# p3_fan_regulator.net
KiCad netlist of a schematic drawn in Altium Designer
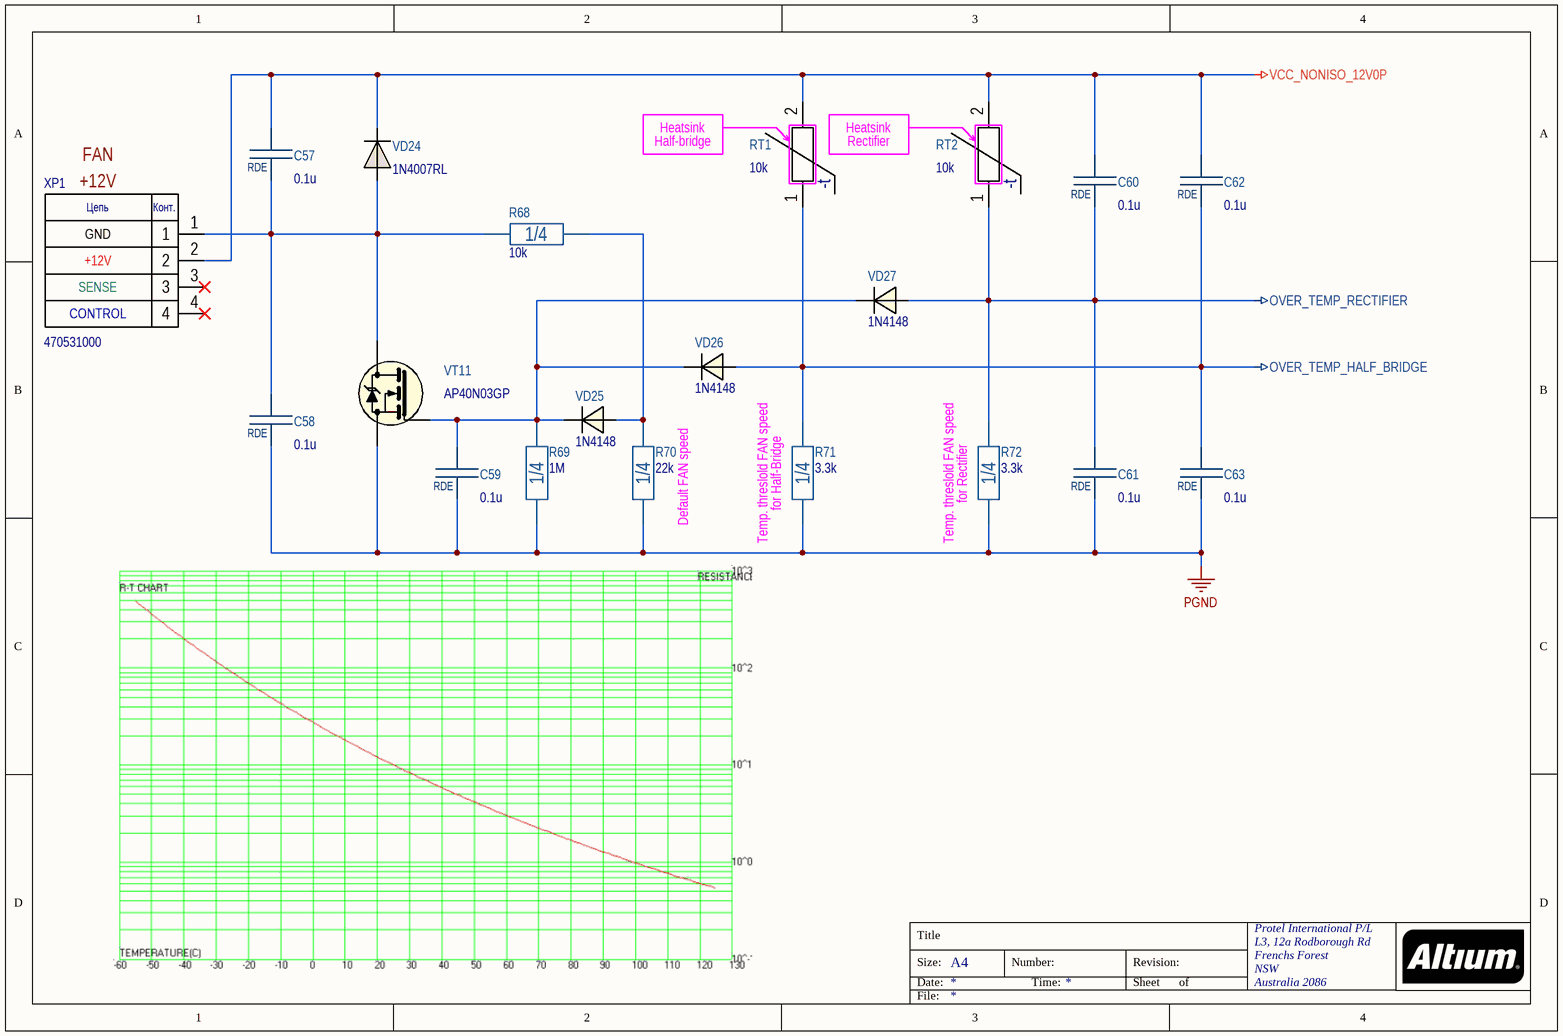
[diagram p0: p3_fan_regulator.SchDoc]

(export (version "E")
  (design (tool "Eeschema 10.0.6"))
  (components
    (comp (ref "C57")
      (value "0.1u")
      (footprint "PcbLib_RC:RDE_1P1")
      (description "MLCC radial lead type with epoxy coat (RDE Series)")
      (fields
        (field (name "TOLERANCE") "± 10 %")
        (field (name "VOLTAGE") "100V")
        (field (name "PACKAGE") "RDE")
      )
      (libsource (lib "Schlib_RC") (part "RDE_CAP"))
    )
    (comp (ref "C58")
      (value "0.1u")
      (footprint "PcbLib_RC:RDE_1P1")
      (description "MLCC radial lead type with epoxy coat (RDE Series)")
      (fields
        (field (name "TOLERANCE") "± 10 %")
        (field (name "VOLTAGE") "100V")
        (field (name "PACKAGE") "RDE")
      )
      (libsource (lib "Schlib_RC") (part "RDE_CAP"))
    )
    (comp (ref "C59")
      (value "0.1u")
      (footprint "PcbLib_RC:RDE_1P1")
      (description "MLCC radial lead type with epoxy coat (RDE Series)")
      (fields
        (field (name "TOLERANCE") "± 10 %")
        (field (name "VOLTAGE") "100V")
        (field (name "PACKAGE") "RDE")
      )
      (libsource (lib "Schlib_RC") (part "RDE_CAP"))
    )
    (comp (ref "C60")
      (value "0.1u")
      (footprint "PcbLib_RC:RDE_1P1")
      (description "MLCC radial lead type with epoxy coat (RDE Series)")
      (fields
        (field (name "TOLERANCE") "± 10 %")
        (field (name "VOLTAGE") "100V")
        (field (name "PACKAGE") "RDE")
      )
      (libsource (lib "Schlib_RC") (part "RDE_CAP"))
    )
    (comp (ref "C61")
      (value "0.1u")
      (footprint "PcbLib_RC:RDE_1P1")
      (description "MLCC radial lead type with epoxy coat (RDE Series)")
      (fields
        (field (name "TOLERANCE") "± 10 %")
        (field (name "VOLTAGE") "100V")
        (field (name "PACKAGE") "RDE")
      )
      (libsource (lib "Schlib_RC") (part "RDE_CAP"))
    )
    (comp (ref "C62")
      (value "0.1u")
      (footprint "PcbLib_RC:RDE_1P1")
      (description "MLCC radial lead type with epoxy coat (RDE Series)")
      (fields
        (field (name "TOLERANCE") "± 10 %")
        (field (name "VOLTAGE") "100V")
        (field (name "PACKAGE") "RDE")
      )
      (libsource (lib "Schlib_RC") (part "RDE_CAP"))
    )
    (comp (ref "C63")
      (value "0.1u")
      (footprint "PcbLib_RC:RDE_1P1")
      (description "MLCC radial lead type with epoxy coat (RDE Series)")
      (fields
        (field (name "TOLERANCE") "± 10 %")
        (field (name "VOLTAGE") "100V")
        (field (name "PACKAGE") "RDE")
      )
      (libsource (lib "Schlib_RC") (part "RDE_CAP"))
    )
    (comp (ref "R68")
      (value "10k")
      (footprint "PcbLib_RC:CFR-25")
      (description "Resistor 1/4W")
      (fields
        (field (name "TOLERANCE") "± 1 %")
        (field (name "PART NUMBER") "MFR-25FTF52-10K")
        (field (name "PACKAGE") "1/4")
      )
      (libsource (lib "Schlib_RC") (part "CF25"))
    )
    (comp (ref "R69")
      (value "1M")
      (footprint "PcbLib_RC:CFR-25(VERTICAL)")
      (description "Resistor 1/4W")
      (fields
        (field (name "TOLERANCE") "± 1 %")
        (field (name "PART NUMBER") "MFR-25FTF52-1M")
        (field (name "PACKAGE") "1/4")
      )
      (libsource (lib "Schlib_RC") (part "CF25"))
    )
    (comp (ref "R70")
      (value "22k")
      (footprint "PcbLib_RC:CFR-25(VERTICAL)")
      (description "Resistor 1/4W")
      (fields
        (field (name "TOLERANCE") "± 1 %")
        (field (name "PART NUMBER") "MFR-25FTF52-22K")
        (field (name "PACKAGE") "1/4")
      )
      (libsource (lib "Schlib_RC") (part "CF25"))
    )
    (comp (ref "R71")
      (value "3.3k")
      (footprint "PcbLib_RC:CFR-25(VERTICAL)")
      (description "Resistor 1/4W")
      (fields
        (field (name "TOLERANCE") "± 1 %")
        (field (name "PART NUMBER") "MFR-25FTF52-3K3")
        (field (name "PACKAGE") "1/4")
      )
      (libsource (lib "Schlib_RC") (part "CF25"))
    )
    (comp (ref "R72")
      (value "3.3k")
      (footprint "PcbLib_RC:CFR-25(VERTICAL)")
      (description "Resistor 1/4W")
      (fields
        (field (name "TOLERANCE") "± 1 %")
        (field (name "PART NUMBER") "MFR-25FTF52-3K3")
        (field (name "PACKAGE") "1/4")
      )
      (libsource (lib "Schlib_RC") (part "CF25"))
    )
    (comp (ref "RT1")
      (value "10k")
      (footprint "PcbLib_Others:NTC_D8")
      (description "NTC thermistors")
      (libsource (lib "Schlib_OtherComponents") (part "NTC"))
    )
    (comp (ref "RT2")
      (value "10k")
      (footprint "PcbLib_Others:NTC_D8")
      (description "NTC thermistors")
      (libsource (lib "Schlib_OtherComponents") (part "NTC"))
    )
    (comp (ref "VD24")
      (value "1N4007RL")
      (footprint "PcbLib_Discrete:DO-41")
      (description "1A 1000V Standard Recovery Rectifiers Diode")
      (fields (field (name "MANUFACTURER") "ON Semiconductor"))
      (libsource (lib "Schlib_ONSemiconductor") (part "1N4007RL"))
    )
    (comp (ref "VD25")
      (value "1N4148")
      (footprint "PcbLib_Discrete:DO-35 GLASS LIGHT RED")
      (description "High-speed diode")
      (libsource (lib "Schlib_NXP_Semiconductors") (part "1N4148"))
    )
    (comp (ref "VD26")
      (value "1N4148")
      (footprint "PcbLib_Discrete:DO-35 GLASS LIGHT RED")
      (description "High-speed diode")
      (libsource (lib "Schlib_NXP_Semiconductors") (part "1N4148"))
    )
    (comp (ref "VD27")
      (value "1N4148")
      (footprint "PcbLib_Discrete:DO-35 GLASS LIGHT RED")
      (description "High-speed diode")
      (libsource (lib "Schlib_NXP_Semiconductors") (part "1N4148"))
    )
    (comp (ref "VT11")
      (value "AP40N03GP")
      (footprint "TO-220A-3")
      (description "N-Channel MOSFET,  30V, 40A")
      (fields (field (name "MANUFACTURER") "Advanced Power Electronics Corp."))
      (libsource (lib "Schlib_OtherComponents") (part "AP40N03GP"))
    )
    (comp (ref "XP1")
      (value "470531000")
      (footprint "PcbLib_Pin_Headers:0470531000")
      (libsource (lib "Schlib_MolexConnectors") (part "470531000"))
    )
  )
  (nets
    (net (code "1") (name "Net-(R68-Pad1)") (class "Default")
      (node (ref "R68") (pin "1") (pinfunction "1_1") (pintype "passive"))
      (node (ref "R70") (pin "2") (pinfunction "2_2") (pintype "passive"))
      (node (ref "VD25") (pin "2") (pinfunction "2_2") (pintype "passive"))
    )
    (net (code "2") (name "Net-(VD24-A)") (class "Default")
      (node (ref "C57") (pin "2") (pinfunction "2_2") (pintype "passive"))
      (node (ref "C58") (pin "1") (pinfunction "1_1") (pintype "passive"))
      (node (ref "R68") (pin "2") (pinfunction "2_2") (pintype "passive"))
      (node (ref "VD24") (pin "2") (pinfunction "A_2") (pintype "passive"))
      (node (ref "VT11") (pin "2") (pinfunction "D_2") (pintype "passive"))
      (node (ref "XP1") (pin "1") (pinfunction "1_1") (pintype "passive"))
    )
    (net (code "3") (name "Net-(VT11-G)") (class "Default")
      (node (ref "C59") (pin "1") (pinfunction "1_1") (pintype "passive"))
      (node (ref "R69") (pin "2") (pinfunction "2_2") (pintype "passive"))
      (node (ref "VD25") (pin "1") (pinfunction "1_1") (pintype "passive"))
      (node (ref "VD26") (pin "1") (pinfunction "1_1") (pintype "passive"))
      (node (ref "VD27") (pin "1") (pinfunction "1_1") (pintype "passive"))
      (node (ref "VT11") (pin "1") (pinfunction "G_1") (pintype "passive"))
    )
    (net (code "4") (name "OVER_TEMP_HALF_BRIDGE") (class "Default")
      (node (ref "C62") (pin "2") (pinfunction "2_2") (pintype "passive"))
      (node (ref "C63") (pin "1") (pinfunction "1_1") (pintype "passive"))
      (node (ref "R71") (pin "2") (pinfunction "2_2") (pintype "passive"))
      (node (ref "RT1") (pin "1") (pinfunction "1_1") (pintype "passive"))
      (node (ref "VD26") (pin "2") (pinfunction "2_2") (pintype "passive"))
    )
    (net (code "5") (name "OVER_TEMP_RECTIFIER") (class "Default")
      (node (ref "C60") (pin "2") (pinfunction "2_2") (pintype "passive"))
      (node (ref "C61") (pin "1") (pinfunction "1_1") (pintype "passive"))
      (node (ref "R72") (pin "2") (pinfunction "2_2") (pintype "passive"))
      (node (ref "RT2") (pin "1") (pinfunction "1_1") (pintype "passive"))
      (node (ref "VD27") (pin "2") (pinfunction "2_2") (pintype "passive"))
    )
    (net (code "6") (name "PGND") (class "Default")
      (node (ref "C58") (pin "2") (pinfunction "2_2") (pintype "passive"))
      (node (ref "C59") (pin "2") (pinfunction "2_2") (pintype "passive"))
      (node (ref "C61") (pin "2") (pinfunction "2_2") (pintype "passive"))
      (node (ref "C63") (pin "2") (pinfunction "2_2") (pintype "passive"))
      (node (ref "R69") (pin "1") (pinfunction "1_1") (pintype "passive"))
      (node (ref "R70") (pin "1") (pinfunction "1_1") (pintype "passive"))
      (node (ref "R71") (pin "1") (pinfunction "1_1") (pintype "passive"))
      (node (ref "R72") (pin "1") (pinfunction "1_1") (pintype "passive"))
      (node (ref "VT11") (pin "3") (pinfunction "S_3") (pintype "passive"))
    )
    (net (code "7") (name "VCC_NONISO_12V0P") (class "Default")
      (node (ref "C57") (pin "1") (pinfunction "1_1") (pintype "passive"))
      (node (ref "C60") (pin "1") (pinfunction "1_1") (pintype "passive"))
      (node (ref "C62") (pin "1") (pinfunction "1_1") (pintype "passive"))
      (node (ref "RT1") (pin "2") (pinfunction "2_2") (pintype "passive"))
      (node (ref "RT2") (pin "2") (pinfunction "2_2") (pintype "passive"))
      (node (ref "VD24") (pin "1") (pinfunction "C_1") (pintype "passive"))
      (node (ref "XP1") (pin "2") (pinfunction "2_2") (pintype "passive"))
    )
    (net (code "8") (name "unconnected-(XP1-Pad3)") (class "Default")
      (node (ref "XP1") (pin "3") (pinfunction "3_3") (pintype "passive+no_connect"))
    )
    (net (code "9") (name "unconnected-(XP1-Pad4)") (class "Default")
      (node (ref "XP1") (pin "4") (pinfunction "4_4") (pintype "passive+no_connect"))
    )
  )
)
